# Car_Power_Supply_2x_Line_v1_0.net
KiCad netlist of a schematic drawn in Altium Designer
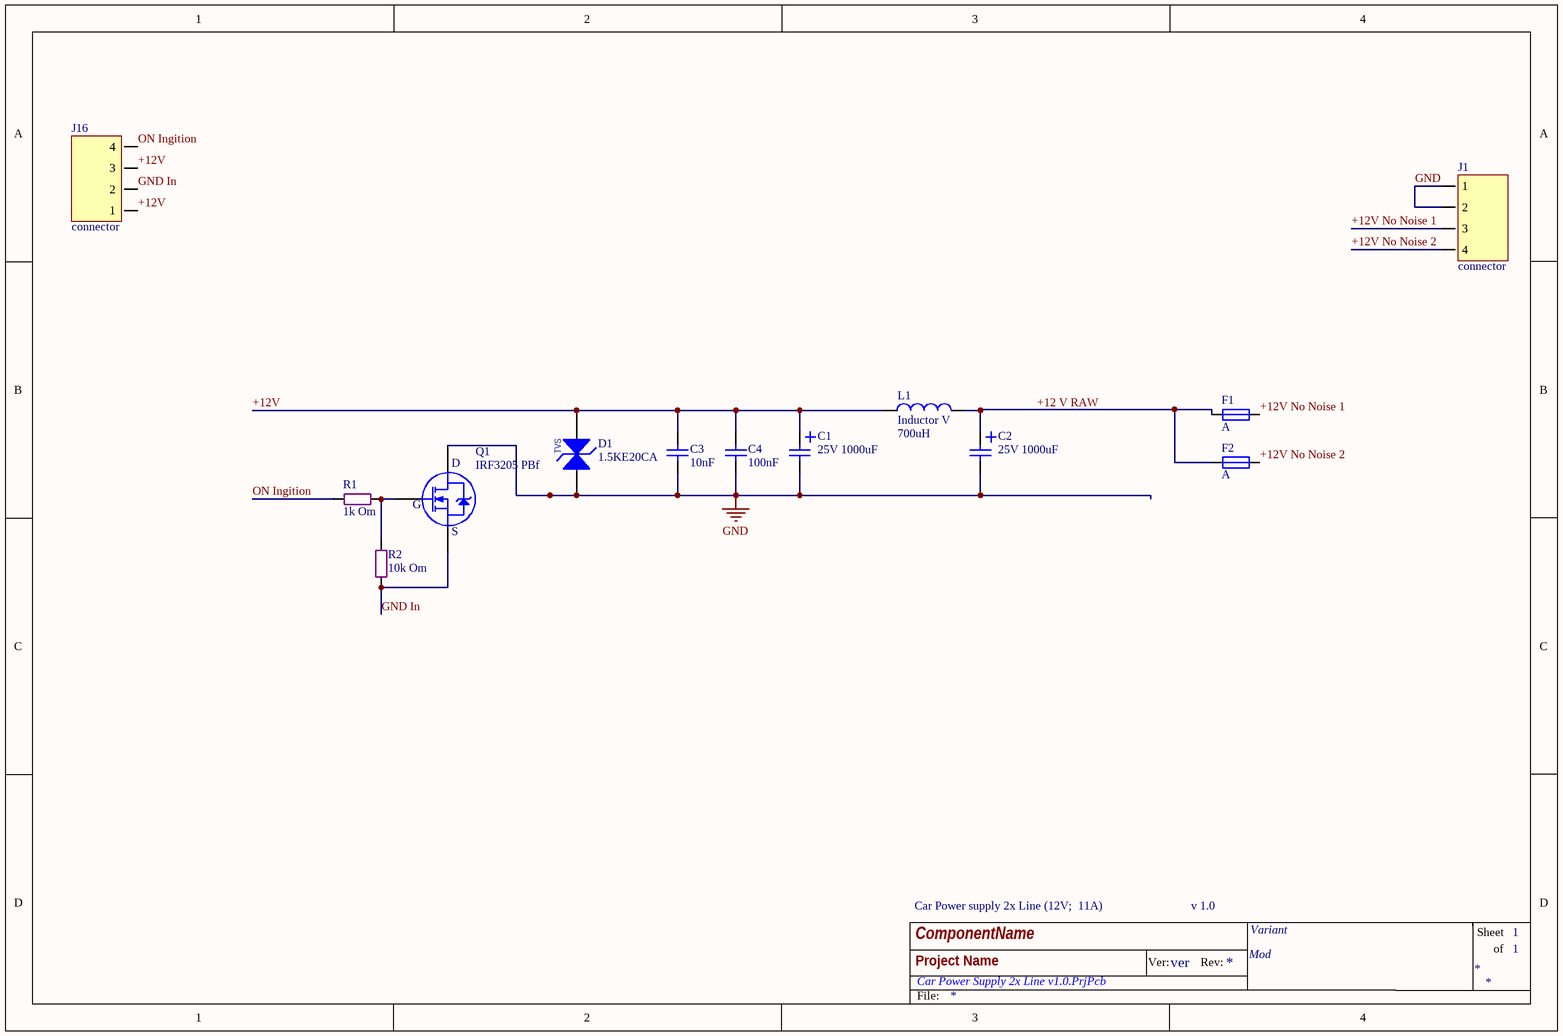
[diagram p0: Car Power Supply 2x Line v1.0.SchDoc]

(export (version "E")
  (design (tool "Eeschema 10.0.6"))
  (components
    (comp (ref "C1")
      (value "25V 1000uF")
      (footprint "Capacitor:Cap E p5.08mm D10.2mm (3p)")
      (description "Capacitor")
      (libsource (lib "Capacitor") (part "Cap E 1000mF x 25V"))
    )
    (comp (ref "C2")
      (value "25V 1000uF")
      (footprint "Capacitor:Cap E p5.08mm D10.2mm (3p)")
      (description "Capacitor")
      (libsource (lib "Capacitor") (part "Cap E 1000mF x 25V"))
    )
    (comp (ref "C3")
      (value "10nF")
      (footprint "Capacitor:SMD 1206 (3216)")
      (description "Capacitor")
      (libsource (lib "Capacitor") (part "Cap Ceramic SMD (All)"))
    )
    (comp (ref "C4")
      (value "100nF")
      (footprint "Capacitor:SMD 1206 (3216)")
      (description "Capacitor")
      (libsource (lib "Capacitor") (part "Cap Ceramic SMD (All)"))
    )
    (comp (ref "D1")
      (value "1.5KE20CA")
      (footprint "Diodes:TVS diode DO-201 V")
      (description "1500W Transil (TVS Diode)")
      (libsource (lib "Diodes") (part "TVS 1.5KE20CA"))
    )
    (comp (ref "F1")
      (value "A")
      (footprint "PassiveComponents:Fuse RGE1100")
      (description "Round fuse")
      (libsource (lib "PassiveComponents") (part "Fuse"))
    )
    (comp (ref "F2")
      (value "A")
      (footprint "PassiveComponents:Fuse RGE1100")
      (description "Round fuse")
      (libsource (lib "PassiveComponents") (part "Fuse"))
    )
    (comp (ref "J1")
      (value "connector")
      (footprint "Connector:Molex Mini-Fit Jr - 4Pin V")
      (description "Right, Dbl line, Female")
      (libsource (lib "") (part "Molex Mini-Fit Jr - 4 pin_1"))
    )
    (comp (ref "J16")
      (value "connector")
      (footprint "Connector:Molex Mini-Fit Jr - 4Pin V")
      (description "Right, Dbl line, Female")
      (libsource (lib "Connector") (part "Molex Mini-Fit Jr - 4 pin"))
    )
    (comp (ref "L1")
      (value "Inductor V")
      (footprint "Transformers:Toroid V D14-W6")
      (description "Inductor Vertical")
      (fields (field (name "ALTIUM_VALUE") "700uH") (field (name "PUBLISHER") "Altium Limited"))
      (libsource (lib "Transformers") (part "Inductor V"))
    )
    (comp (ref "Q1")
      (value "IRF3205 PBf")
      (footprint "GeneralCases:TO220-2 HighPower")
      (description "N-Channel 55V - 0.008Ω - 110A")
      (libsource (lib "Transistor") (part "IRF3205"))
    )
    (comp (ref "R1")
      (value "1k Om")
      (footprint "PassiveComponents:SMD 0805 (2012)")
      (libsource (lib "PassiveComponents") (part "Res All Types"))
    )
    (comp (ref "R2")
      (value "10k Om")
      (footprint "PassiveComponents:SMD 0805 (2012)")
      (libsource (lib "PassiveComponents") (part "Res All Types"))
    )
  )
  (nets
    (net (code "2") (name "/+12V") (class "Default")
      (node (ref "C1") (pin "1") (pinfunction "1_1") (pintype "passive"))
      (node (ref "C3") (pin "1") (pinfunction "1_1") (pintype "passive"))
      (node (ref "C4") (pin "1") (pinfunction "1_1") (pintype "passive"))
      (node (ref "D1") (pin "2") (pinfunction "2_2") (pintype "passive"))
      (node (ref "J16") (pin "1") (pinfunction "1_1") (pintype "passive"))
      (node (ref "J16") (pin "3") (pinfunction "3_3") (pintype "passive"))
      (node (ref "L1") (pin "1") (pinfunction "1_1") (pintype "passive"))
    )
    (net (code "3") (name "/+12V No Noise 1") (class "Default")
      (node (ref "F1") (pin "2") (pinfunction "2_2") (pintype "passive"))
      (node (ref "J1") (pin "3") (pinfunction "3_3") (pintype "passive"))
    )
    (net (code "4") (name "/+12V No Noise 2") (class "Default")
      (node (ref "F2") (pin "2") (pinfunction "2_2") (pintype "passive"))
      (node (ref "J1") (pin "4") (pinfunction "4_4") (pintype "passive"))
    )
    (net (code "5") (name "/GND In") (class "Default")
      (node (ref "J16") (pin "2") (pinfunction "2_2") (pintype "passive"))
      (node (ref "Q1") (pin "3") (pinfunction "S_3") (pintype "passive"))
      (node (ref "R2") (pin "1") (pinfunction "1_1") (pintype "passive"))
    )
    (net (code "6") (name "/ON Ingition") (class "Default")
      (node (ref "J16") (pin "4") (pinfunction "4_4") (pintype "passive"))
      (node (ref "R1") (pin "1") (pinfunction "1_1") (pintype "passive"))
    )
    (net (code "7") (name "GND") (class "Default")
      (node (ref "C1") (pin "2") (pinfunction "2_2") (pintype "passive"))
      (node (ref "C2") (pin "2") (pinfunction "2_2") (pintype "passive"))
      (node (ref "C3") (pin "2") (pinfunction "2_2") (pintype "passive"))
      (node (ref "C4") (pin "2") (pinfunction "2_2") (pintype "passive"))
      (node (ref "D1") (pin "1") (pinfunction "1_1") (pintype "passive"))
      (node (ref "J1") (pin "1") (pinfunction "1_1") (pintype "passive"))
      (node (ref "J1") (pin "2") (pinfunction "2_2") (pintype "passive"))
      (node (ref "Q1") (pin "2") (pinfunction "D_2") (pintype "passive"))
    )
    (net (code "8") (name "Net-(C2-Pad1)") (class "Default")
      (node (ref "C2") (pin "1") (pinfunction "1_1") (pintype "passive"))
      (node (ref "F1") (pin "1") (pinfunction "1_1") (pintype "passive"))
      (node (ref "F2") (pin "1") (pinfunction "1_1") (pintype "passive"))
      (node (ref "L1") (pin "2") (pinfunction "2_2") (pintype "passive"))
    )
    (net (code "9") (name "Net-(Q1-G)") (class "Default")
      (node (ref "Q1") (pin "1") (pinfunction "G_1") (pintype "passive"))
      (node (ref "R1") (pin "2") (pinfunction "2_2") (pintype "passive"))
      (node (ref "R2") (pin "2") (pinfunction "2_2") (pintype "passive"))
    )
  )
)
